# medusa-AI-audio.net
KiCad netlist of a schematic drawn in Altium Designer
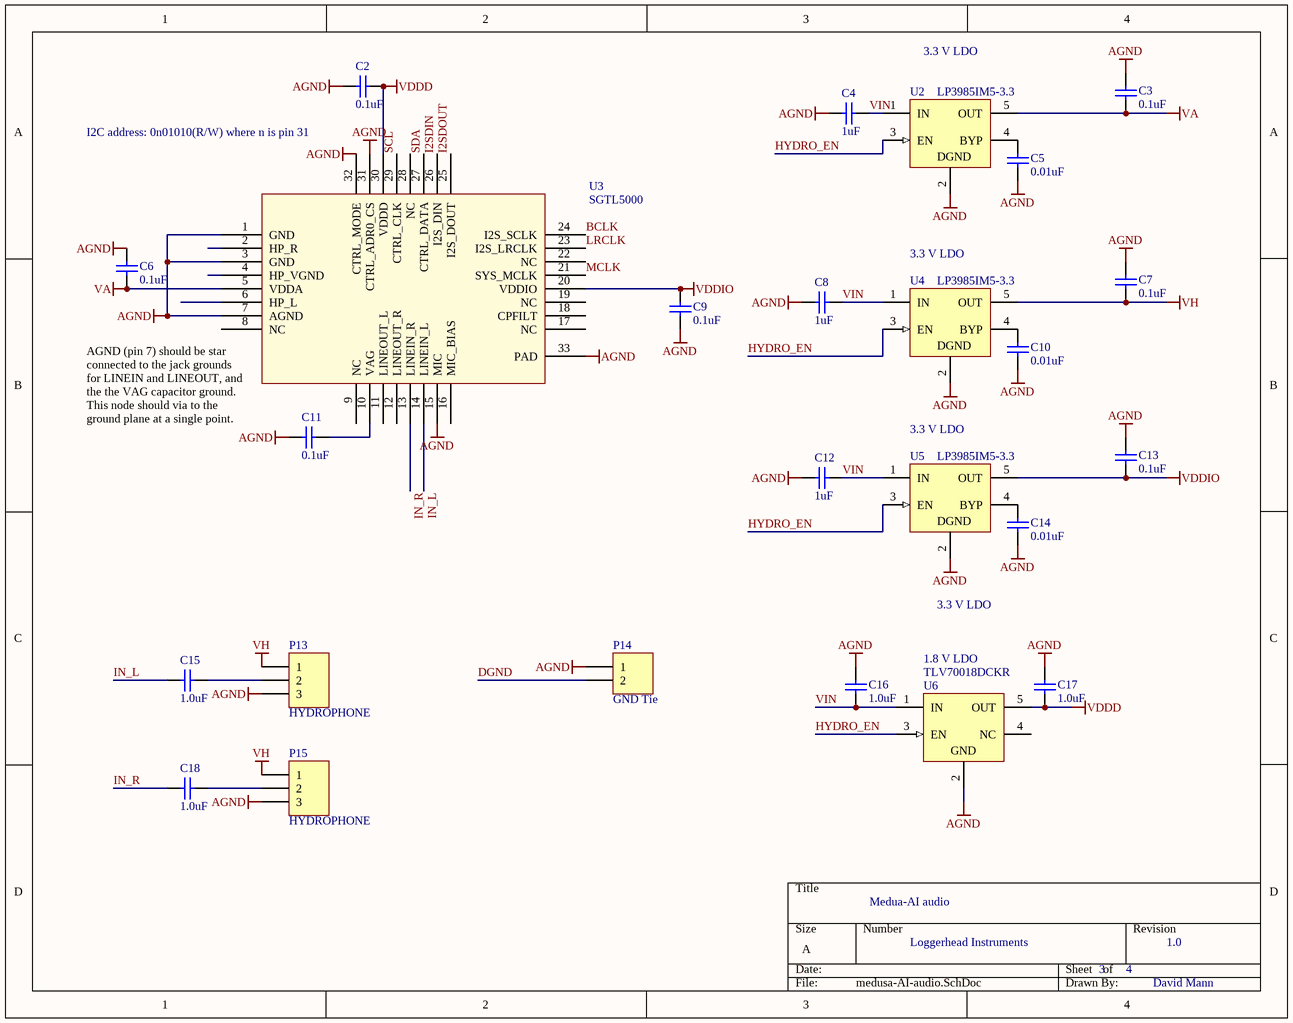
[diagram p0: medusa-AI-audio.SchDoc]

(export (version "E")
  (design (tool "Eeschema 10.0.6"))
  (components
    (comp (ref "C2")
      (value "0.1uF")
      (footprint "0402")
      (description "Ceramic Chip Capacitor - Standard")
      (fields (field (name "PUBLISHER") "Altium Limited"))
      (libsource (lib "KEMET Chip Capacitor") (part "C0402"))
    )
    (comp (ref "C3")
      (value "0.1uF")
      (footprint "0402")
      (description "Ceramic Chip Capacitor - Standard")
      (fields (field (name "PUBLISHER") "Altium Limited"))
      (libsource (lib "KEMET Chip Capacitor") (part "C0402"))
    )
    (comp (ref "C4")
      (value "1uF")
      (footprint "0402")
      (description "Ceramic Chip Capacitor - Standard")
      (fields (field (name "PUBLISHER") "Altium Limited"))
      (libsource (lib "KEMET Chip Capacitor") (part "C0402"))
    )
    (comp (ref "C5")
      (value "0.01uF")
      (footprint "0402")
      (description "Ceramic Chip Capacitor - Standard")
      (fields (field (name "PUBLISHER") "Altium Limited"))
      (libsource (lib "KEMET Chip Capacitor") (part "C0402"))
    )
    (comp (ref "C6")
      (value "0.1uF")
      (footprint "0402")
      (description "Ceramic Chip Capacitor - Standard")
      (fields (field (name "PUBLISHER") "Altium Limited"))
      (libsource (lib "KEMET Chip Capacitor") (part "C0402"))
    )
    (comp (ref "C7")
      (value "0.1uF")
      (footprint "0402")
      (description "Ceramic Chip Capacitor - Standard")
      (fields (field (name "PUBLISHER") "Altium Limited"))
      (libsource (lib "KEMET Chip Capacitor") (part "C0402"))
    )
    (comp (ref "C8")
      (value "1uF")
      (footprint "0402")
      (description "Ceramic Chip Capacitor - Standard")
      (fields (field (name "PUBLISHER") "Altium Limited"))
      (libsource (lib "KEMET Chip Capacitor") (part "C0402"))
    )
    (comp (ref "C9")
      (value "0.1uF")
      (footprint "0402")
      (description "Ceramic Chip Capacitor - Standard")
      (fields (field (name "PUBLISHER") "Altium Limited"))
      (libsource (lib "KEMET Chip Capacitor") (part "C0402"))
    )
    (comp (ref "C10")
      (value "0.01uF")
      (footprint "0402")
      (description "Ceramic Chip Capacitor - Standard")
      (fields (field (name "PUBLISHER") "Altium Limited"))
      (libsource (lib "KEMET Chip Capacitor") (part "C0402"))
    )
    (comp (ref "C11")
      (value "0.1uF")
      (footprint "0402")
      (description "Ceramic Chip Capacitor - Standard")
      (fields (field (name "PUBLISHER") "Altium Limited"))
      (libsource (lib "KEMET Chip Capacitor") (part "C0402"))
    )
    (comp (ref "C12")
      (value "1uF")
      (footprint "0402")
      (description "Ceramic Chip Capacitor - Standard")
      (fields (field (name "PUBLISHER") "Altium Limited"))
      (libsource (lib "KEMET Chip Capacitor") (part "C0402"))
    )
    (comp (ref "C13")
      (value "0.1uF")
      (footprint "0402")
      (description "Ceramic Chip Capacitor - Standard")
      (fields (field (name "PUBLISHER") "Altium Limited"))
      (libsource (lib "KEMET Chip Capacitor") (part "C0402"))
    )
    (comp (ref "C14")
      (value "0.01uF")
      (footprint "0402")
      (description "Ceramic Chip Capacitor - Standard")
      (fields (field (name "PUBLISHER") "Altium Limited"))
      (libsource (lib "KEMET Chip Capacitor") (part "C0402"))
    )
    (comp (ref "C15")
      (value "1.0uF")
      (footprint "0402")
      (description "Ceramic Chip Capacitor - Standard")
      (fields (field (name "PUBLISHER") "Altium Limited"))
      (libsource (lib "KEMET Chip Capacitor") (part "C0402"))
    )
    (comp (ref "C16")
      (value "1.0uF")
      (footprint "0402")
      (description "Ceramic Chip Capacitor - Standard")
      (fields (field (name "PUBLISHER") "Altium Limited"))
      (libsource (lib "KEMET Chip Capacitor") (part "C0402"))
    )
    (comp (ref "C17")
      (value "1.0uF")
      (footprint "0402")
      (description "Ceramic Chip Capacitor - Standard")
      (fields (field (name "PUBLISHER") "Altium Limited"))
      (libsource (lib "KEMET Chip Capacitor") (part "C0402"))
    )
    (comp (ref "C18")
      (value "1.0uF")
      (footprint "0402")
      (description "Ceramic Chip Capacitor - Standard")
      (fields (field (name "PUBLISHER") "Altium Limited"))
      (libsource (lib "KEMET Chip Capacitor") (part "C0402"))
    )
    (comp (ref "P13")
      (value "HYDROPHONE")
      (footprint "HDR1X3")
      (description "Header, 3-Pin")
      (fields (field (name "PUBLISHER") "Altium Limited"))
      (libsource (lib "Miscellaneous Connectors") (part "Header 3"))
    )
    (comp (ref "P14")
      (value "GND Tie")
      (footprint "HDR1X2")
      (description "Header, 2-Pin")
      (fields (field (name "PUBLISHER") "Altium Limited"))
      (libsource (lib "Miscellaneous Connectors") (part "Header 2"))
    )
    (comp (ref "P15")
      (value "HYDROPHONE")
      (footprint "HDR1X3")
      (description "Header, 3-Pin")
      (fields (field (name "PUBLISHER") "Altium Limited"))
      (libsource (lib "Miscellaneous Connectors") (part "Header 3"))
    )
    (comp (ref "U2")
      (value "LP3985IM5-3.3")
      (footprint "MF05A_N")
      (description "Micropower, 150mA Low-Noise Ultra Low-Dropout CMOS Voltage Regulator")
      (fields
        (field (name "MANUFACTURER") "National Semiconductor")
        (field (name "DIGIKEYPARTNUMBER") "LP3985IM5-3.3CT-ND")
        (field (name "PUBLISHER") "Altium Limited")
      )
      (libsource (lib "NSC LDO") (part "LP3985IM5-3.3"))
    )
    (comp (ref "U3") (value "SGTL5000") (footprint "QFN32") (libsource (lib "Loggerhead") (part "SGTL5000")))
    (comp (ref "U4")
      (value "LP3985IM5-3.3")
      (footprint "MF05A_N")
      (description "Micropower, 150mA Low-Noise Ultra Low-Dropout CMOS Voltage Regulator")
      (fields
        (field (name "MANUFACTURER") "National Semiconductor")
        (field (name "DIGIKEYPARTNUMBER") "LP3985IM5-3.3CT-ND")
        (field (name "PUBLISHER") "Altium Limited")
      )
      (libsource (lib "NSC LDO") (part "LP3985IM5-3.3"))
    )
    (comp (ref "U5")
      (value "LP3985IM5-3.3")
      (footprint "MF05A_N")
      (description "Micropower, 150mA Low-Noise Ultra Low-Dropout CMOS Voltage Regulator")
      (fields
        (field (name "MANUFACTURER") "National Semiconductor")
        (field (name "DIGIKEYPARTNUMBER") "LP3985IM5-3.3CT-ND")
        (field (name "PUBLISHER") "Altium Limited")
      )
      (libsource (lib "NSC LDO") (part "LP3985IM5-3.3"))
    )
    (comp (ref "U6")
      (value "TLV70018DCKR")
      (footprint "TI-DCK5_V")
      (fields (field (name "MANUFACTURER") "Texas Instruments"))
      (libsource (lib "TI Power Management Linear Regulator Single Channel LDO (0-350mA)") (part "TLV70018DCKR"))
    )
  )
  (nets
    (net (code "1") (name "/BCLK") (class "Default")
      (node (ref "U3") (pin "24") (pinfunction "I2S_SCLK_24") (pintype "passive"))
    )
    (net (code "2") (name "/DGND") (class "Default")
      (node (ref "P14") (pin "2") (pinfunction "2_2") (pintype "passive"))
    )
    (net (code "3") (name "/HYDRO_EN") (class "Default")
      (node (ref "U2") (pin "3") (pinfunction "EN_3") (pintype "input"))
      (node (ref "U4") (pin "3") (pinfunction "EN_3") (pintype "input"))
      (node (ref "U5") (pin "3") (pinfunction "EN_3") (pintype "input"))
      (node (ref "U6") (pin "3") (pinfunction "EN_3") (pintype "input"))
    )
    (net (code "4") (name "/I2SDIN") (class "Default")
      (node (ref "U3") (pin "26") (pinfunction "I2S_DIN_26") (pintype "passive"))
    )
    (net (code "5") (name "/I2SDOUT") (class "Default")
      (node (ref "U3") (pin "25") (pinfunction "I2S_DOUT_25") (pintype "passive"))
    )
    (net (code "6") (name "/IN_L") (class "Default")
      (node (ref "C15") (pin "2") (pinfunction "2_2") (pintype "passive"))
      (node (ref "U3") (pin "14") (pinfunction "LINEIN_L_14") (pintype "passive"))
    )
    (net (code "7") (name "/IN_R") (class "Default")
      (node (ref "C18") (pin "2") (pinfunction "2_2") (pintype "passive"))
      (node (ref "U3") (pin "13") (pinfunction "LINEIN_R_13") (pintype "passive"))
    )
    (net (code "8") (name "/LRCLK") (class "Default")
      (node (ref "U3") (pin "23") (pinfunction "I2S_LRCLK_23") (pintype "passive"))
    )
    (net (code "9") (name "/MCLK") (class "Default")
      (node (ref "U3") (pin "21") (pinfunction "SYS_MCLK_21") (pintype "passive"))
    )
    (net (code "10") (name "/SCL") (class "Default")
      (node (ref "U3") (pin "29") (pinfunction "CTRL_CLK_29") (pintype "passive"))
    )
    (net (code "11") (name "/SDA") (class "Default")
      (node (ref "U3") (pin "27") (pinfunction "CTRL_DATA_27") (pintype "passive"))
    )
    (net (code "12") (name "/VIN") (class "Default")
      (node (ref "C12") (pin "1") (pinfunction "1_1") (pintype "passive"))
      (node (ref "C16") (pin "1") (pinfunction "1_1") (pintype "passive"))
      (node (ref "C4") (pin "1") (pinfunction "1_1") (pintype "passive"))
      (node (ref "C8") (pin "1") (pinfunction "1_1") (pintype "passive"))
      (node (ref "U2") (pin "1") (pinfunction "IN_1") (pintype "power_in"))
      (node (ref "U4") (pin "1") (pinfunction "IN_1") (pintype "power_in"))
      (node (ref "U5") (pin "1") (pinfunction "IN_1") (pintype "power_in"))
      (node (ref "U6") (pin "1") (pinfunction "IN_1") (pintype "power_in"))
    )
    (net (code "13") (name "AGND") (class "Default")
      (node (ref "C10") (pin "2") (pinfunction "2_2") (pintype "passive"))
      (node (ref "C11") (pin "2") (pinfunction "2_2") (pintype "passive"))
      (node (ref "C12") (pin "2") (pinfunction "2_2") (pintype "passive"))
      (node (ref "C13") (pin "2") (pinfunction "2_2") (pintype "passive"))
      (node (ref "C14") (pin "2") (pinfunction "2_2") (pintype "passive"))
      (node (ref "C16") (pin "2") (pinfunction "2_2") (pintype "passive"))
      (node (ref "C17") (pin "2") (pinfunction "2_2") (pintype "passive"))
      (node (ref "C2") (pin "2") (pinfunction "2_2") (pintype "passive"))
      (node (ref "C3") (pin "2") (pinfunction "2_2") (pintype "passive"))
      (node (ref "C4") (pin "2") (pinfunction "2_2") (pintype "passive"))
      (node (ref "C5") (pin "2") (pinfunction "2_2") (pintype "passive"))
      (node (ref "C6") (pin "2") (pinfunction "2_2") (pintype "passive"))
      (node (ref "C7") (pin "2") (pinfunction "2_2") (pintype "passive"))
      (node (ref "C8") (pin "2") (pinfunction "2_2") (pintype "passive"))
      (node (ref "C9") (pin "2") (pinfunction "2_2") (pintype "passive"))
      (node (ref "P13") (pin "3") (pinfunction "3_3") (pintype "passive"))
      (node (ref "P14") (pin "1") (pinfunction "1_1") (pintype "passive"))
      (node (ref "P15") (pin "3") (pinfunction "3_3") (pintype "passive"))
      (node (ref "U2") (pin "2") (pinfunction "GND_2") (pintype "power_in"))
      (node (ref "U3") (pin "1") (pinfunction "GND_1") (pintype "passive"))
      (node (ref "U3") (pin "15") (pinfunction "MIC_15") (pintype "passive"))
      (node (ref "U3") (pin "3") (pinfunction "GND_3") (pintype "passive"))
      (node (ref "U3") (pin "31") (pinfunction "CTRL_ADR0_CS_31") (pintype "passive"))
      (node (ref "U3") (pin "32") (pinfunction "CTRL_MODE_32") (pintype "passive"))
      (node (ref "U3") (pin "33") (pinfunction "PAD_33") (pintype "passive"))
      (node (ref "U3") (pin "7") (pinfunction "AGND_7") (pintype "passive"))
      (node (ref "U4") (pin "2") (pinfunction "GND_2") (pintype "power_in"))
      (node (ref "U5") (pin "2") (pinfunction "GND_2") (pintype "power_in"))
      (node (ref "U6") (pin "2") (pinfunction "GND_2") (pintype "power_in"))
    )
    (net (code "14") (name "Net-(C15-Pad1)") (class "Default")
      (node (ref "C15") (pin "1") (pinfunction "1_1") (pintype "passive"))
      (node (ref "P13") (pin "2") (pinfunction "2_2") (pintype "passive"))
    )
    (net (code "15") (name "Net-(C18-Pad1)") (class "Default")
      (node (ref "C18") (pin "1") (pinfunction "1_1") (pintype "passive"))
      (node (ref "P15") (pin "2") (pinfunction "2_2") (pintype "passive"))
    )
    (net (code "16") (name "Net-(U2-BYP)") (class "Default")
      (node (ref "C5") (pin "1") (pinfunction "1_1") (pintype "passive"))
      (node (ref "U2") (pin "4") (pinfunction "BYP_4") (pintype "passive"))
    )
    (net (code "17") (name "Net-(U3-VAG)") (class "Default")
      (node (ref "C11") (pin "1") (pinfunction "1_1") (pintype "passive"))
      (node (ref "U3") (pin "10") (pinfunction "VAG_10") (pintype "passive"))
    )
    (net (code "18") (name "Net-(U4-BYP)") (class "Default")
      (node (ref "C10") (pin "1") (pinfunction "1_1") (pintype "passive"))
      (node (ref "U4") (pin "4") (pinfunction "BYP_4") (pintype "passive"))
    )
    (net (code "19") (name "Net-(U5-BYP)") (class "Default")
      (node (ref "C14") (pin "1") (pinfunction "1_1") (pintype "passive"))
      (node (ref "U5") (pin "4") (pinfunction "BYP_4") (pintype "passive"))
    )
    (net (code "20") (name "VA") (class "Default")
      (node (ref "C3") (pin "1") (pinfunction "1_1") (pintype "passive"))
      (node (ref "C6") (pin "1") (pinfunction "1_1") (pintype "passive"))
      (node (ref "U2") (pin "5") (pinfunction "OUT_5") (pintype "power_in"))
      (node (ref "U3") (pin "5") (pinfunction "VDDA_5") (pintype "passive"))
    )
    (net (code "21") (name "VDDD") (class "Default")
      (node (ref "C17") (pin "1") (pinfunction "1_1") (pintype "passive"))
      (node (ref "C2") (pin "1") (pinfunction "1_1") (pintype "passive"))
      (node (ref "U3") (pin "30") (pinfunction "VDDD_30") (pintype "passive"))
      (node (ref "U6") (pin "5") (pinfunction "OUT_5") (pintype "power_in"))
    )
    (net (code "22") (name "VDDIO") (class "Default")
      (node (ref "C13") (pin "1") (pinfunction "1_1") (pintype "passive"))
      (node (ref "C9") (pin "1") (pinfunction "1_1") (pintype "passive"))
      (node (ref "U3") (pin "20") (pinfunction "VDDIO_20") (pintype "passive"))
      (node (ref "U5") (pin "5") (pinfunction "OUT_5") (pintype "power_in"))
    )
    (net (code "23") (name "VH") (class "Default")
      (node (ref "C7") (pin "1") (pinfunction "1_1") (pintype "passive"))
      (node (ref "P13") (pin "1") (pinfunction "1_1") (pintype "passive"))
      (node (ref "P15") (pin "1") (pinfunction "1_1") (pintype "passive"))
      (node (ref "U4") (pin "5") (pinfunction "OUT_5") (pintype "power_in"))
    )
    (net (code "24") (name "unconnected-(U3-CPFILT-Pad18)") (class "Default")
      (node (ref "U3") (pin "18") (pinfunction "CPFILT_18") (pintype "passive"))
    )
    (net (code "25") (name "unconnected-(U3-HP_L-Pad6)") (class "Default")
      (node (ref "U3") (pin "6") (pinfunction "HP_L_6") (pintype "passive"))
    )
    (net (code "26") (name "unconnected-(U3-HP_R-Pad2)") (class "Default")
      (node (ref "U3") (pin "2") (pinfunction "HP_R_2") (pintype "passive"))
    )
    (net (code "27") (name "unconnected-(U3-HP_VGND-Pad4)") (class "Default")
      (node (ref "U3") (pin "4") (pinfunction "HP_VGND_4") (pintype "passive"))
    )
    (net (code "28") (name "unconnected-(U3-LINEOUT_L-Pad11)") (class "Default")
      (node (ref "U3") (pin "11") (pinfunction "LINEOUT_L_11") (pintype "passive"))
    )
    (net (code "29") (name "unconnected-(U3-LINEOUT_R-Pad12)") (class "Default")
      (node (ref "U3") (pin "12") (pinfunction "LINEOUT_R_12") (pintype "passive"))
    )
    (net (code "30") (name "unconnected-(U3-MIC_BIAS-Pad16)") (class "Default")
      (node (ref "U3") (pin "16") (pinfunction "MIC_BIAS_16") (pintype "passive"))
    )
    (net (code "31") (name "unconnected-(U3-NC-Pad8)") (class "Default")
      (node (ref "U3") (pin "8") (pinfunction "NC_8") (pintype "passive"))
    )
    (net (code "32") (name "unconnected-(U3-NC-Pad9)") (class "Default")
      (node (ref "U3") (pin "9") (pinfunction "NC_9") (pintype "passive"))
    )
    (net (code "33") (name "unconnected-(U3-NC-Pad17)") (class "Default")
      (node (ref "U3") (pin "17") (pinfunction "NC_17") (pintype "passive"))
    )
    (net (code "34") (name "unconnected-(U3-NC-Pad19)") (class "Default")
      (node (ref "U3") (pin "19") (pinfunction "NC_19") (pintype "passive"))
    )
    (net (code "35") (name "unconnected-(U3-NC-Pad22)") (class "Default")
      (node (ref "U3") (pin "22") (pinfunction "NC_22") (pintype "passive"))
    )
    (net (code "36") (name "unconnected-(U3-NC-Pad28)") (class "Default")
      (node (ref "U3") (pin "28") (pinfunction "NC_28") (pintype "passive"))
    )
    (net (code "37") (name "unconnected-(U6-NC-Pad4)") (class "Default")
      (node (ref "U6") (pin "4") (pinfunction "NC_4") (pintype "passive"))
    )
  )
)
